# analog_gpio.net
KiCad netlist of a schematic drawn in Altium Designer
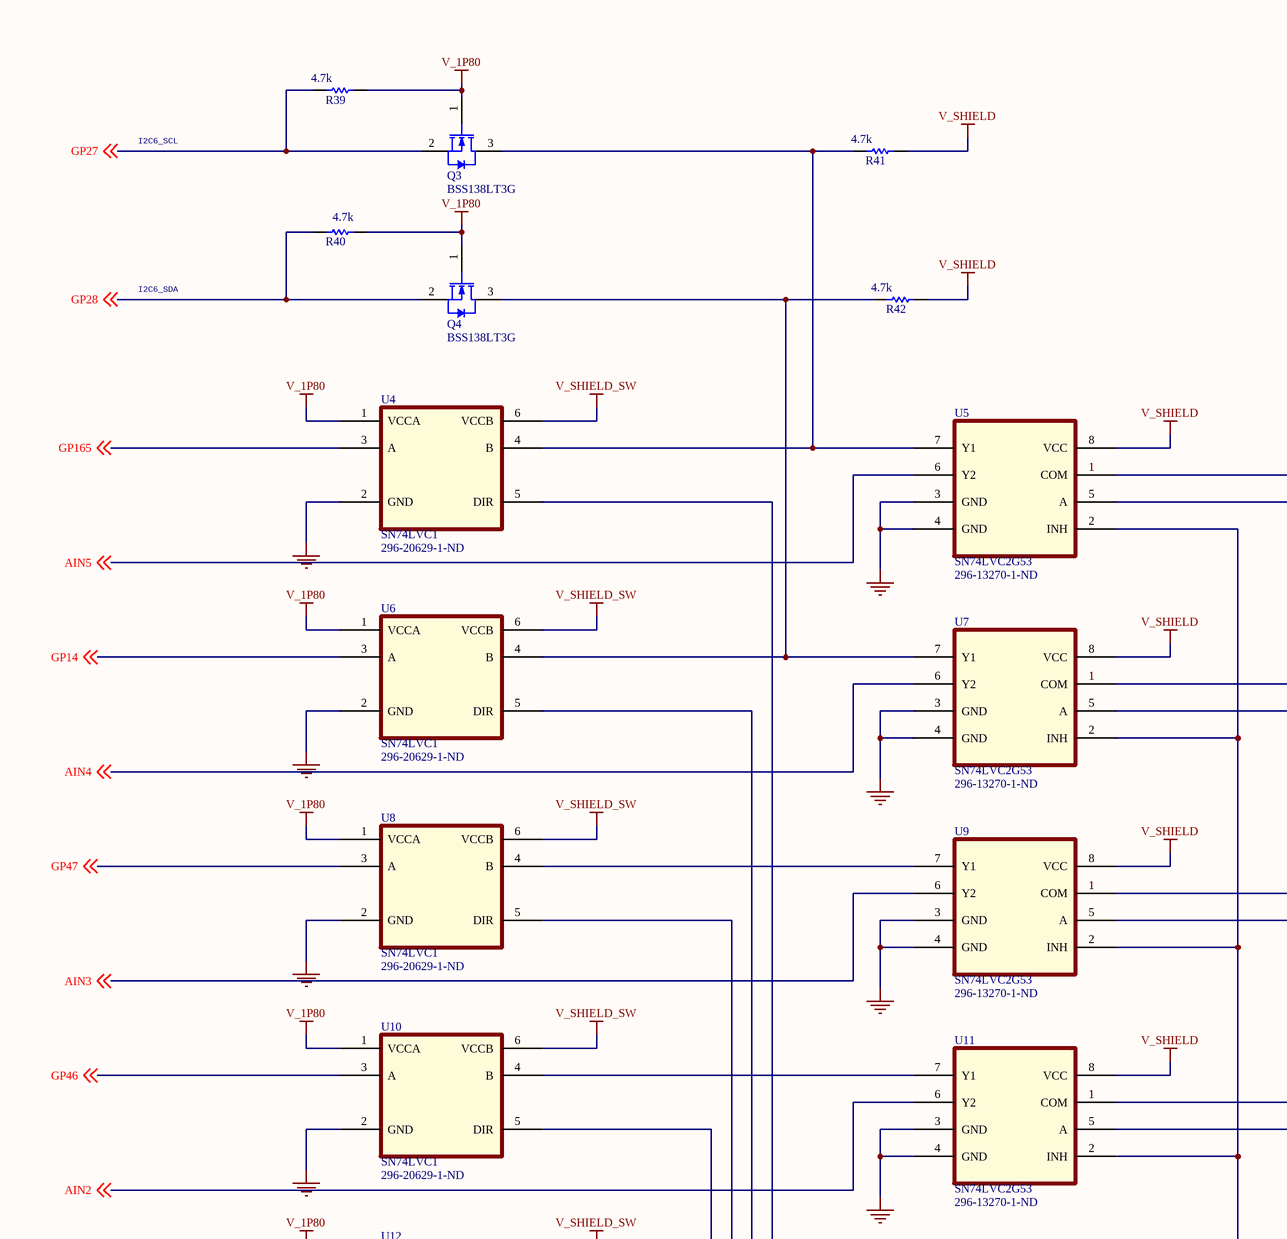
[diagram p0: analog_gpio.SchDoc, top left]
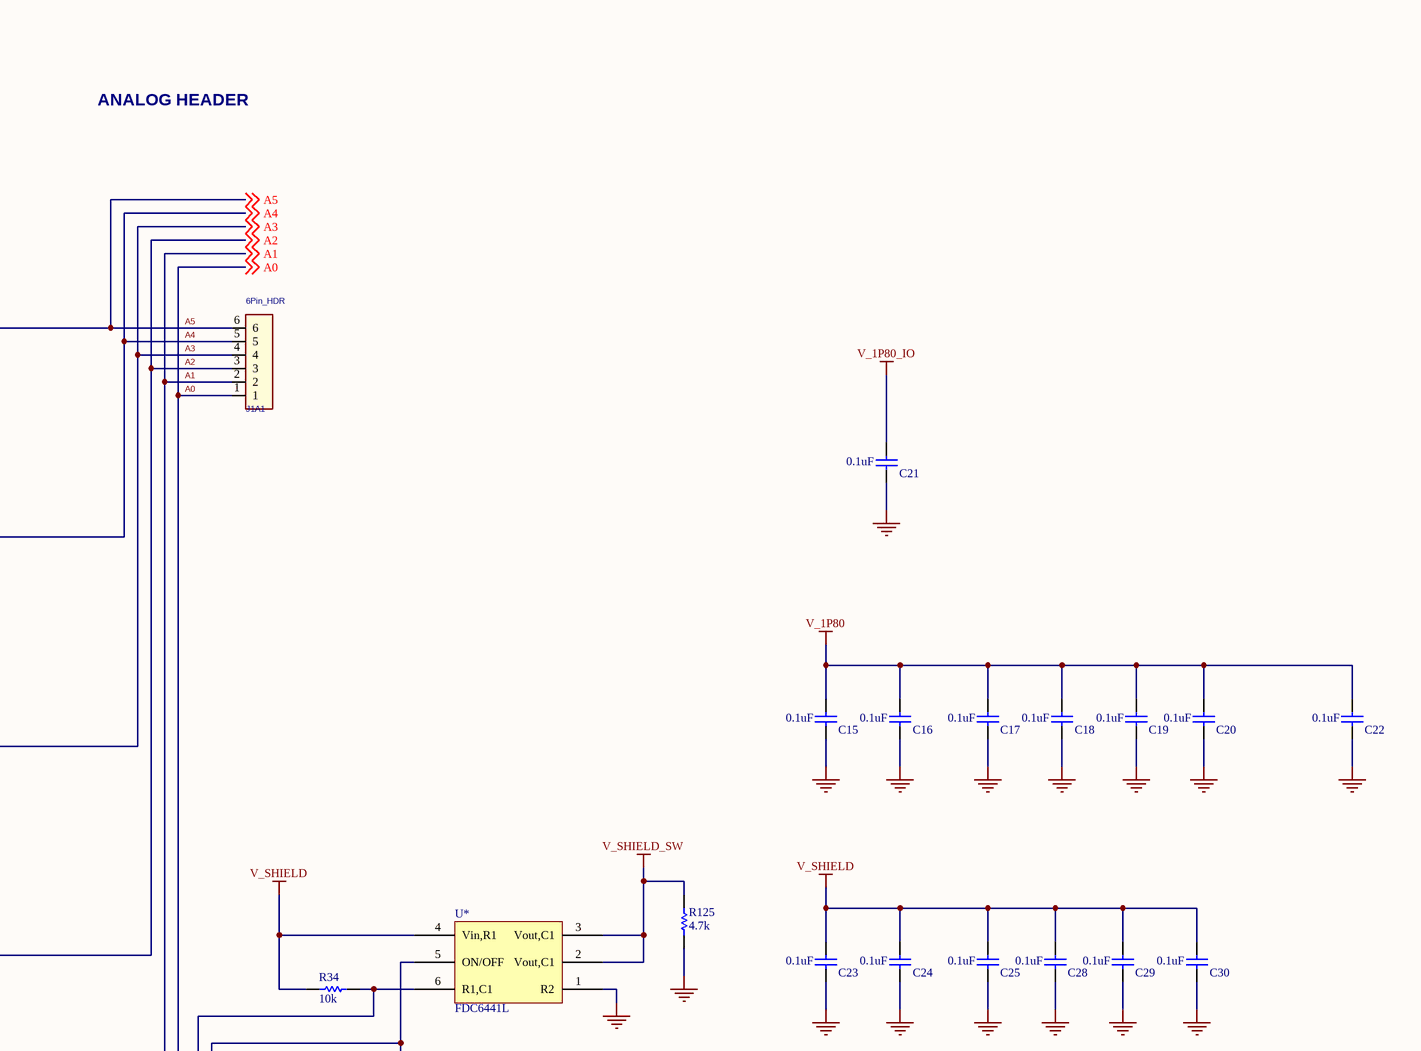
[diagram p1: analog_gpio.SchDoc, top right]
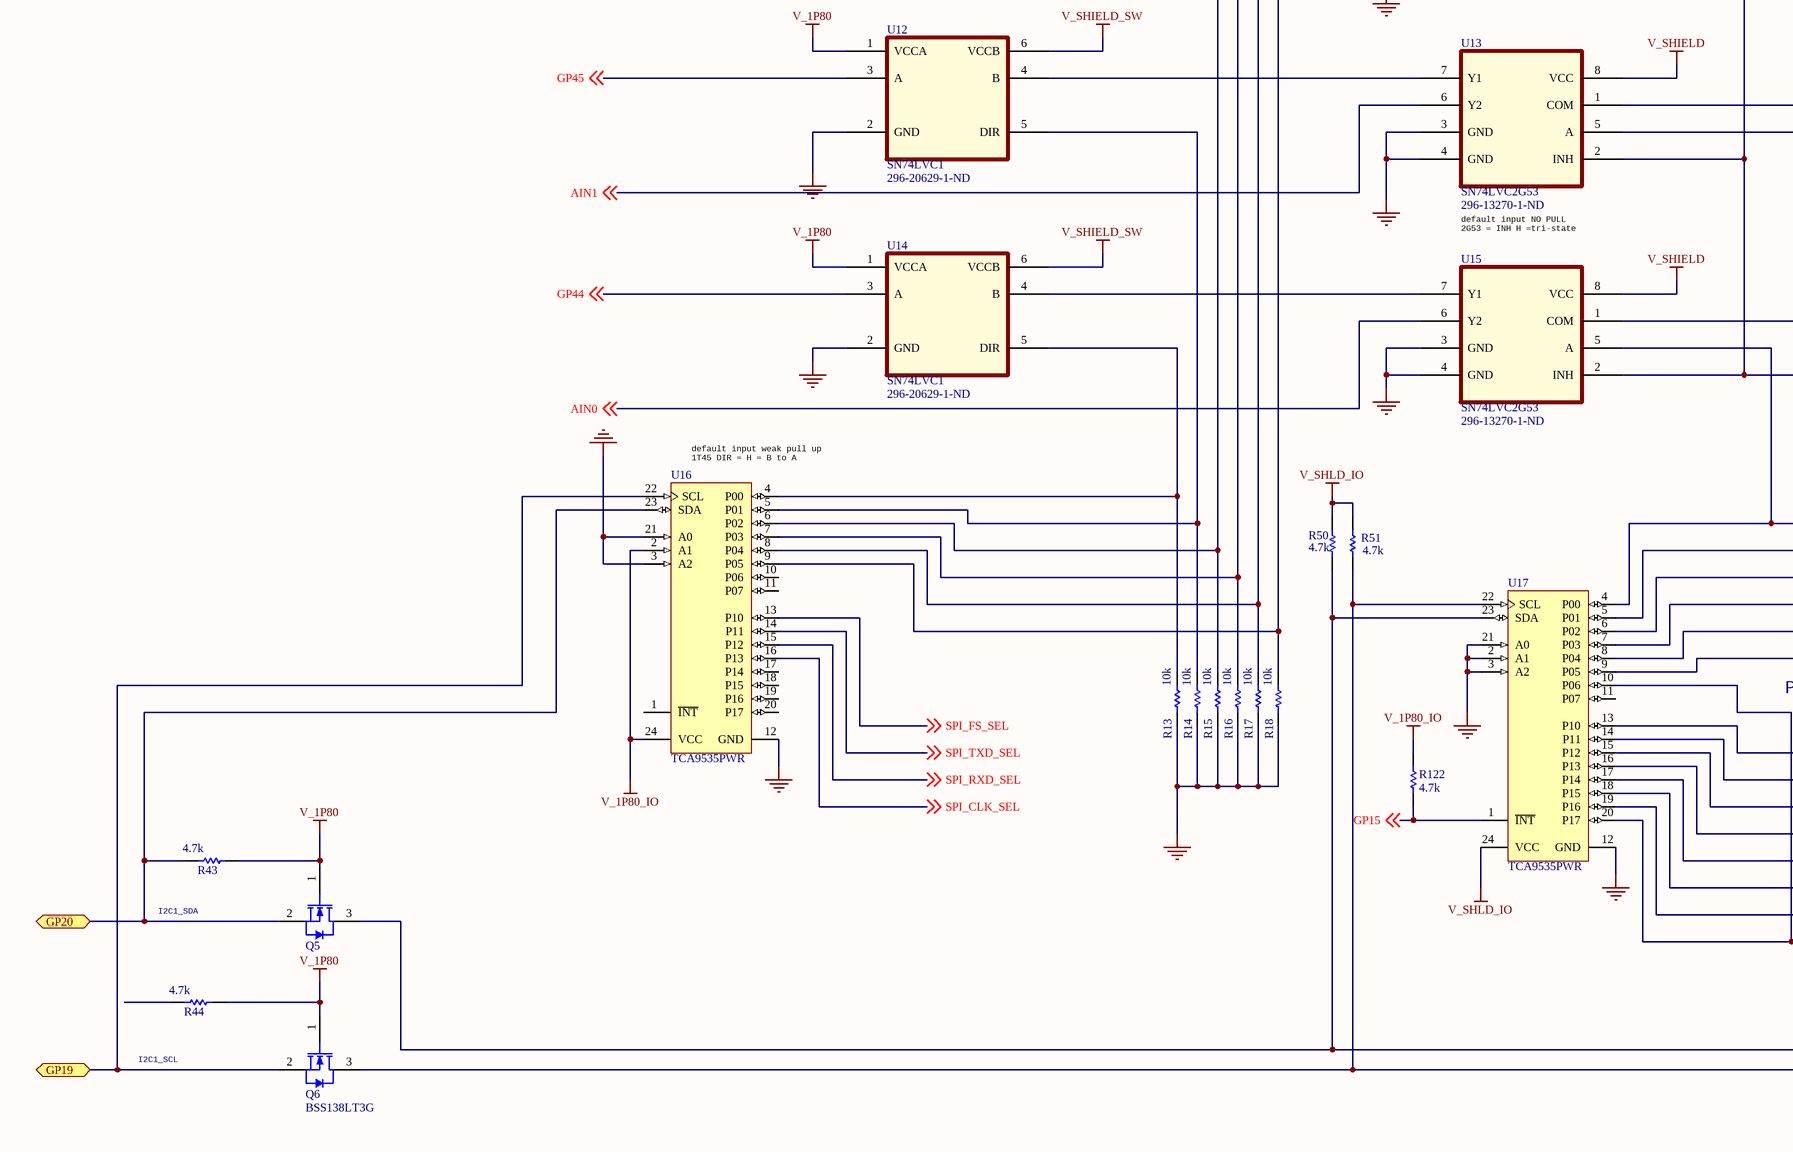
[diagram p2: analog_gpio.SchDoc, bottom left]
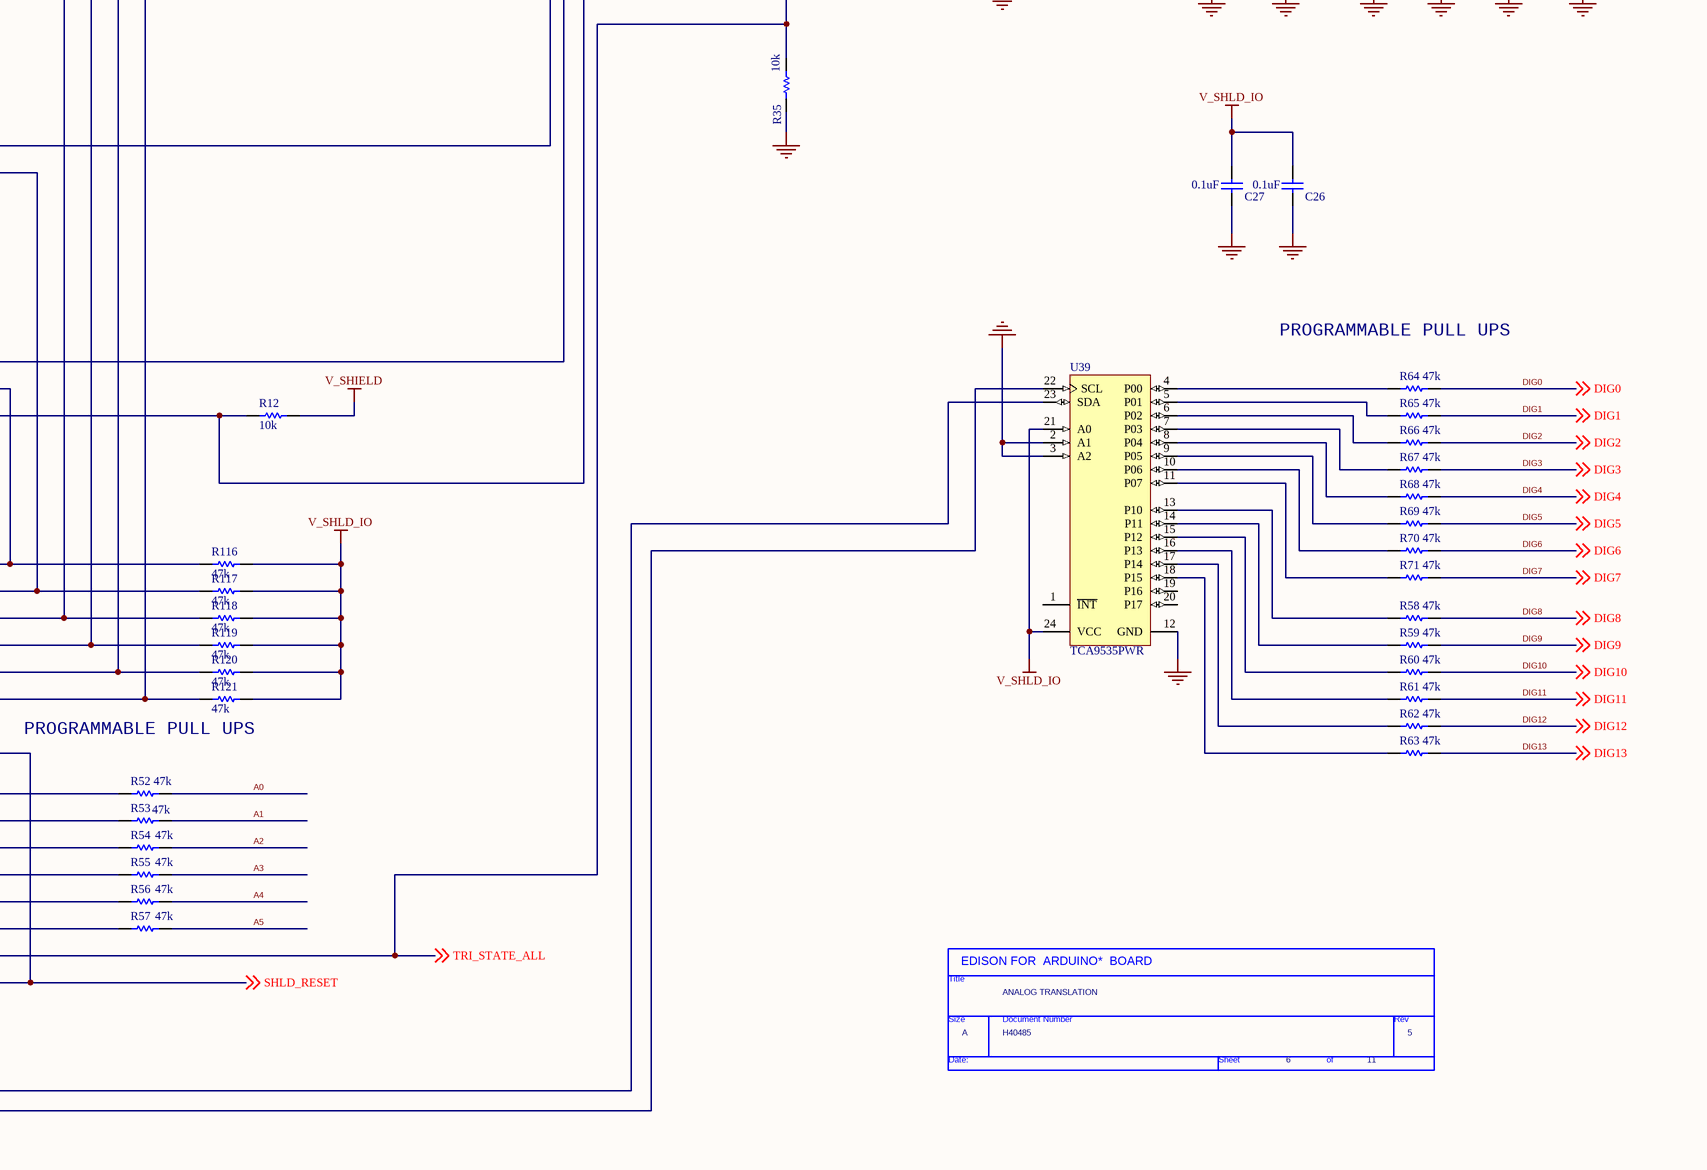
[diagram p3: analog_gpio.SchDoc, bottom right]

(export (version "E")
  (design (tool "Eeschema 10.0.6"))
  (components
    (comp (ref "*")
      (value "TitleBlock0")
      (fields
        (field (name "PAGE COUNT") "11")
        (field (name "PAGE NUMBER") "6")
        (field (name "PAGE SIZE") "A")
        (field (name "TITLE") "ANALOG TRANSLATION")
        (field (name "REVCODE") "5")
        (field (name "DOC") "H40485")
      )
      (libsource (lib "*") (part "TitleBlock0"))
    )
    (comp (ref "C15")
      (value "0.1uF")
      (footprint "CAPC0201(0603)33_L")
      (description "CAP 1.5nF 10V ±20% 0201 (0603 Metric) Thickness 0.33mm SMD")
      (fields (field (name "TOLERANCE") "±20%") (field (name "Comment") "CAP 1.5nF 10V 0201(0603)"))
      (libsource (lib "Altium Content Vault") (part "CMP-1033-00601-1"))
    )
    (comp (ref "C16")
      (value "0.1uF")
      (footprint "CAPC0201(0603)33_L")
      (description "CAP 1.5nF 10V ±20% 0201 (0603 Metric) Thickness 0.33mm SMD")
      (fields (field (name "TOLERANCE") "±20%") (field (name "Comment") "CAP 1.5nF 10V 0201(0603)"))
      (libsource (lib "Altium Content Vault") (part "CMP-1033-00601-1"))
    )
    (comp (ref "C17")
      (value "0.1uF")
      (footprint "CAPC0201(0603)33_L")
      (description "CAP 1.5nF 10V ±20% 0201 (0603 Metric) Thickness 0.33mm SMD")
      (fields (field (name "TOLERANCE") "±20%") (field (name "Comment") "CAP 1.5nF 10V 0201(0603)"))
      (libsource (lib "Altium Content Vault") (part "CMP-1033-00601-1"))
    )
    (comp (ref "C18")
      (value "0.1uF")
      (footprint "CAPC0201(0603)33_L")
      (description "CAP 1.5nF 10V ±20% 0201 (0603 Metric) Thickness 0.33mm SMD")
      (fields (field (name "TOLERANCE") "±20%") (field (name "Comment") "CAP 1.5nF 10V 0201(0603)"))
      (libsource (lib "Altium Content Vault") (part "CMP-1033-00601-1"))
    )
    (comp (ref "C19")
      (value "0.1uF")
      (footprint "CAPC0201(0603)33_L")
      (description "CAP 1.5nF 10V ±20% 0201 (0603 Metric) Thickness 0.33mm SMD")
      (fields (field (name "TOLERANCE") "±20%") (field (name "Comment") "CAP 1.5nF 10V 0201(0603)"))
      (libsource (lib "Altium Content Vault") (part "CMP-1033-00601-1"))
    )
    (comp (ref "C20")
      (value "0.1uF")
      (footprint "CAPC0201(0603)33_L")
      (description "CAP 1.5nF 10V ±20% 0201 (0603 Metric) Thickness 0.33mm SMD")
      (fields (field (name "TOLERANCE") "±20%") (field (name "Comment") "CAP 1.5nF 10V 0201(0603)"))
      (libsource (lib "Altium Content Vault") (part "CMP-1033-00601-1"))
    )
    (comp (ref "C21")
      (value "0.1uF")
      (footprint "CAPC0201(0603)33_L")
      (description "CAP 1.5nF 10V ±20% 0201 (0603 Metric) Thickness 0.33mm SMD")
      (fields (field (name "TOLERANCE") "±20%") (field (name "Comment") "CAP 1.5nF 10V 0201(0603)"))
      (libsource (lib "Altium Content Vault") (part "CMP-1033-00601-1"))
    )
    (comp (ref "C22")
      (value "0.1uF")
      (footprint "CAPC0201(0603)33_L")
      (description "CAP 1.5nF 10V ±20% 0201 (0603 Metric) Thickness 0.33mm SMD")
      (fields (field (name "TOLERANCE") "±20%") (field (name "Comment") "CAP 1.5nF 10V 0201(0603)"))
      (libsource (lib "Altium Content Vault") (part "CMP-1033-00601-1"))
    )
    (comp (ref "C23")
      (value "0.1uF")
      (footprint "CAPC0201(0603)33_L")
      (description "CAP 1.5nF 10V ±20% 0201 (0603 Metric) Thickness 0.33mm SMD")
      (fields (field (name "TOLERANCE") "±20%") (field (name "Comment") "CAP 1.5nF 10V 0201(0603)"))
      (libsource (lib "Altium Content Vault") (part "CMP-1033-00601-1"))
    )
    (comp (ref "C24")
      (value "0.1uF")
      (footprint "CAPC0201(0603)33_L")
      (description "CAP 1.5nF 10V ±20% 0201 (0603 Metric) Thickness 0.33mm SMD")
      (fields (field (name "TOLERANCE") "±20%") (field (name "Comment") "CAP 1.5nF 10V 0201(0603)"))
      (libsource (lib "Altium Content Vault") (part "CMP-1033-00601-1"))
    )
    (comp (ref "C25")
      (value "0.1uF")
      (footprint "CAPC0201(0603)33_L")
      (description "CAP 1.5nF 10V ±20% 0201 (0603 Metric) Thickness 0.33mm SMD")
      (fields (field (name "TOLERANCE") "±20%") (field (name "Comment") "CAP 1.5nF 10V 0201(0603)"))
      (libsource (lib "Altium Content Vault") (part "CMP-1033-00601-1"))
    )
    (comp (ref "C26")
      (value "0.1uF")
      (footprint "CAPC0201(0603)33_L")
      (description "CAP 1.5nF 10V ±20% 0201 (0603 Metric) Thickness 0.33mm SMD")
      (fields (field (name "TOLERANCE") "±20%") (field (name "Comment") "CAP 1.5nF 10V 0201(0603)"))
      (libsource (lib "Altium Content Vault") (part "CMP-1033-00601-1"))
    )
    (comp (ref "C27")
      (value "0.1uF")
      (footprint "CAPC0201(0603)33_L")
      (description "CAP 1.5nF 10V ±20% 0201 (0603 Metric) Thickness 0.33mm SMD")
      (fields (field (name "TOLERANCE") "±20%") (field (name "Comment") "CAP 1.5nF 10V 0201(0603)"))
      (libsource (lib "Altium Content Vault") (part "CMP-1033-00601-1"))
    )
    (comp (ref "C28")
      (value "0.1uF")
      (footprint "CAPC0201(0603)33_L")
      (description "CAP 1.5nF 10V ±20% 0201 (0603 Metric) Thickness 0.33mm SMD")
      (fields (field (name "TOLERANCE") "±20%") (field (name "Comment") "CAP 1.5nF 10V 0201(0603)"))
      (libsource (lib "Altium Content Vault") (part "CMP-1033-00601-1"))
    )
    (comp (ref "C29")
      (value "0.1uF")
      (footprint "CAPC0201(0603)33_L")
      (description "CAP 1.5nF 10V ±20% 0201 (0603 Metric) Thickness 0.33mm SMD")
      (fields (field (name "TOLERANCE") "±20%") (field (name "Comment") "CAP 1.5nF 10V 0201(0603)"))
      (libsource (lib "Altium Content Vault") (part "CMP-1033-00601-1"))
    )
    (comp (ref "C30")
      (value "0.1uF")
      (footprint "CAPC0201(0603)33_L")
      (description "CAP 1.5nF 10V ±20% 0201 (0603 Metric) Thickness 0.33mm SMD")
      (fields (field (name "TOLERANCE") "±20%") (field (name "Comment") "CAP 1.5nF 10V 0201(0603)"))
      (libsource (lib "Altium Content Vault") (part "CMP-1033-00601-1"))
    )
    (comp (ref "J1A1")
      (value "6Pin_HDR")
      (footprint "109728-038")
      (description "CONN,PLUG,VERT,1X6,2.54MM,THM,90147_1106")
      (fields (field (name "PART_NUMBER") "H46111-001"))
      (libsource (lib "*") (part "CON6,HDR,TH,0.1in,C77962-001"))
    )
    (comp (ref "Q3")
      (value "BSS138LT3G")
      (footprint "ONSC-SOT-23-3-318-08_V")
      (description "Power MOSFET, 200 mA, 50 V, N-Channel, 3-Pin SOT-23, Pb-Free, Tape and Reel")
      (fields (field (name "MANUFACTURER") "On Semiconductor"))
      (libsource (lib "Altium Content Vault") (part "CMP-1058-00765-1"))
    )
    (comp (ref "Q4")
      (value "BSS138LT3G")
      (footprint "ONSC-SOT-23-3-318-08_V")
      (description "Power MOSFET, 200 mA, 50 V, N-Channel, 3-Pin SOT-23, Pb-Free, Tape and Reel")
      (fields (field (name "MANUFACTURER") "On Semiconductor"))
      (libsource (lib "Altium Content Vault") (part "ONSC-NMOS-G1S2D3-3"))
    )
    (comp (ref "Q5")
      (value "BSS138LT3G")
      (footprint "ONSC-SOT-23-3-318-08_V")
      (description "Power MOSFET, 200 mA, 50 V, N-Channel, 3-Pin SOT-23, Pb-Free, Tape and Reel")
      (fields (field (name "MANUFACTURER") "On Semiconductor"))
      (libsource (lib "Altium Content Vault") (part "CMP-1058-00765-1"))
    )
    (comp (ref "Q6")
      (value "BSS138LT3G")
      (footprint "ONSC-SOT-23-3-318-08_V")
      (description "Power MOSFET, 200 mA, 50 V, N-Channel, 3-Pin SOT-23, Pb-Free, Tape and Reel")
      (fields (field (name "MANUFACTURER") "On Semiconductor"))
      (libsource (lib "Altium Content Vault") (part "CMP-1058-00765-1"))
    )
    (comp (ref "R12")
      (value "10k")
      (footprint "RESC0201(0603)_M")
      (description "165R 0.05W 1% 0201 (0603 Metric)  SMD")
      (fields (field (name "POWER") "0.05 W") (field (name "TOLERANCE") "1 %"))
      (libsource (lib "Altium Content Vault") (part "CMP-1010-00326-1"))
    )
    (comp (ref "R13")
      (value "10k")
      (footprint "RESC0201(0603)_M")
      (description "165R 0.05W 1% 0201 (0603 Metric)  SMD")
      (fields (field (name "POWER") "0.05 W") (field (name "TOLERANCE") "1 %"))
      (libsource (lib "Altium Content Vault") (part "CMP-1010-00326-1"))
    )
    (comp (ref "R14")
      (value "10k")
      (footprint "RESC0201(0603)_M")
      (description "165R 0.05W 1% 0201 (0603 Metric)  SMD")
      (fields (field (name "POWER") "0.05 W") (field (name "TOLERANCE") "1 %"))
      (libsource (lib "Altium Content Vault") (part "CMP-1010-00326-1"))
    )
    (comp (ref "R15")
      (value "10k")
      (footprint "RESC0201(0603)_M")
      (description "165R 0.05W 1% 0201 (0603 Metric)  SMD")
      (fields (field (name "POWER") "0.05 W") (field (name "TOLERANCE") "1 %"))
      (libsource (lib "Altium Content Vault") (part "CMP-1010-00326-1"))
    )
    (comp (ref "R16")
      (value "10k")
      (footprint "RESC0201(0603)_M")
      (description "165R 0.05W 1% 0201 (0603 Metric)  SMD")
      (fields (field (name "POWER") "0.05 W") (field (name "TOLERANCE") "1 %"))
      (libsource (lib "Altium Content Vault") (part "CMP-1010-00326-1"))
    )
    (comp (ref "R17")
      (value "10k")
      (footprint "RESC0201(0603)_M")
      (description "165R 0.05W 1% 0201 (0603 Metric)  SMD")
      (fields (field (name "POWER") "0.05 W") (field (name "TOLERANCE") "1 %"))
      (libsource (lib "Altium Content Vault") (part "CMP-1010-00326-1"))
    )
    (comp (ref "R18")
      (value "10k")
      (footprint "RESC0201(0603)_M")
      (description "165R 0.05W 1% 0201 (0603 Metric)  SMD")
      (fields (field (name "POWER") "0.05 W") (field (name "TOLERANCE") "1 %"))
      (libsource (lib "Altium Content Vault") (part "CMP-1010-00326-1"))
    )
    (comp (ref "R34")
      (value "10k")
      (footprint "RESC0201(0603)_M")
      (description "165R 0.05W 1% 0201 (0603 Metric)  SMD")
      (fields (field (name "POWER") "0.05 W") (field (name "TOLERANCE") "1 %"))
      (libsource (lib "Altium Content Vault") (part "CMP-1010-00326-1"))
    )
    (comp (ref "R35")
      (value "10k")
      (footprint "RESC0201(0603)_M")
      (description "165R 0.05W 1% 0201 (0603 Metric)  SMD")
      (fields (field (name "POWER") "0.05 W") (field (name "TOLERANCE") "1 %"))
      (libsource (lib "Altium Content Vault") (part "CMP-1010-00326-1"))
    )
    (comp (ref "R39")
      (value "4.7k")
      (footprint "RESC0201(0603)_N")
      (description "4K7 0.05W 1% 0201 (0603 Metric)  SMD")
      (fields (field (name "TOLERANCE") "1 %") (field (name "POWER") "0.05 W"))
      (libsource (lib "Altium Content Vault") (part "CMP-1010-00492-1"))
    )
    (comp (ref "R40")
      (value "4.7k")
      (footprint "RESC0201(0603)_N")
      (description "4K7 0.05W 1% 0201 (0603 Metric)  SMD")
      (fields (field (name "TOLERANCE") "1 %") (field (name "POWER") "0.05 W"))
      (libsource (lib "Altium Content Vault") (part "CMP-1010-00492-1"))
    )
    (comp (ref "R41")
      (value "4.7k")
      (footprint "RESC0201(0603)_N")
      (description "4K7 0.05W 1% 0201 (0603 Metric)  SMD")
      (fields (field (name "TOLERANCE") "1 %") (field (name "POWER") "0.05 W"))
      (libsource (lib "Altium Content Vault") (part "CMP-1010-00492-1"))
    )
    (comp (ref "R42")
      (value "4.7k")
      (footprint "RESC0201(0603)_N")
      (description "4K7 0.05W 1% 0201 (0603 Metric)  SMD")
      (fields (field (name "TOLERANCE") "1 %") (field (name "POWER") "0.05 W"))
      (libsource (lib "Altium Content Vault") (part "CMP-1010-00492-1"))
    )
    (comp (ref "R43")
      (value "4.7k")
      (footprint "RESC0201(0603)_N")
      (description "4K7 0.05W 1% 0201 (0603 Metric)  SMD")
      (fields (field (name "TOLERANCE") "1 %") (field (name "POWER") "0.05 W"))
      (libsource (lib "Altium Content Vault") (part "CMP-1010-00492-1"))
    )
    (comp (ref "R44")
      (value "4.7k")
      (footprint "RESC0201(0603)_N")
      (description "4K7 0.05W 1% 0201 (0603 Metric)  SMD")
      (fields (field (name "TOLERANCE") "1 %") (field (name "POWER") "0.05 W"))
      (libsource (lib "Altium Content Vault") (part "CMP-1010-00492-1"))
    )
    (comp (ref "R50")
      (value "4.7k")
      (footprint "RESC0201(0603)_N")
      (description "4K7 0.05W 1% 0201 (0603 Metric)  SMD")
      (fields (field (name "TOLERANCE") "1 %") (field (name "POWER") "0.05 W"))
      (libsource (lib "Altium Content Vault") (part "CMP-1010-00492-1"))
    )
    (comp (ref "R51")
      (value "4.7k")
      (footprint "RESC0201(0603)_N")
      (description "4K7 0.05W 1% 0201 (0603 Metric)  SMD")
      (fields (field (name "TOLERANCE") "1 %") (field (name "POWER") "0.05 W"))
      (libsource (lib "Altium Content Vault") (part "CMP-1010-00492-1"))
    )
    (comp (ref "R52")
      (value "47k")
      (footprint "RESC0201(0603)_N")
      (description "47K 0.05W 1% 0201 (0603 Metric)  SMD")
      (fields (field (name "TOLERANCE") "1 %") (field (name "POWER") "0.05 W"))
      (libsource (lib "Altium Content Vault") (part "CMP-1010-00605-1"))
    )
    (comp (ref "R53")
      (value "47k")
      (footprint "RESC0201(0603)_N")
      (description "47K 0.05W 1% 0201 (0603 Metric)  SMD")
      (fields (field (name "TOLERANCE") "1 %") (field (name "POWER") "0.05 W"))
      (libsource (lib "Altium Content Vault") (part "CMP-1010-00605-1"))
    )
    (comp (ref "R54")
      (value "47k")
      (footprint "RESC0201(0603)_N")
      (description "47K 0.05W 1% 0201 (0603 Metric)  SMD")
      (fields (field (name "TOLERANCE") "1 %") (field (name "POWER") "0.05 W"))
      (libsource (lib "Altium Content Vault") (part "CMP-1010-00605-1"))
    )
    (comp (ref "R55")
      (value "47k")
      (footprint "RESC0201(0603)_N")
      (description "47K 0.05W 1% 0201 (0603 Metric)  SMD")
      (fields (field (name "TOLERANCE") "1 %") (field (name "POWER") "0.05 W"))
      (libsource (lib "Altium Content Vault") (part "CMP-1010-00605-1"))
    )
    (comp (ref "R56")
      (value "47k")
      (footprint "RESC0201(0603)_N")
      (description "47K 0.05W 1% 0201 (0603 Metric)  SMD")
      (fields (field (name "TOLERANCE") "1 %") (field (name "POWER") "0.05 W"))
      (libsource (lib "Altium Content Vault") (part "CMP-1010-00605-1"))
    )
    (comp (ref "R57")
      (value "47k")
      (footprint "RESC0201(0603)_N")
      (description "47K 0.05W 1% 0201 (0603 Metric)  SMD")
      (fields (field (name "TOLERANCE") "1 %") (field (name "POWER") "0.05 W"))
      (libsource (lib "Altium Content Vault") (part "CMP-1010-00605-1"))
    )
    (comp (ref "R58")
      (value "47k")
      (footprint "RESC0201(0603)_N")
      (description "47K 0.05W 1% 0201 (0603 Metric)  SMD")
      (fields (field (name "TOLERANCE") "1 %") (field (name "POWER") "0.05 W"))
      (libsource (lib "Altium Content Vault") (part "CMP-1010-00605-1"))
    )
    (comp (ref "R59")
      (value "47k")
      (footprint "RESC0201(0603)_N")
      (description "47K 0.05W 1% 0201 (0603 Metric)  SMD")
      (fields (field (name "TOLERANCE") "1 %") (field (name "POWER") "0.05 W"))
      (libsource (lib "Altium Content Vault") (part "CMP-1010-00605-1"))
    )
    (comp (ref "R60")
      (value "47k")
      (footprint "RESC0201(0603)_N")
      (description "47K 0.05W 1% 0201 (0603 Metric)  SMD")
      (fields (field (name "TOLERANCE") "1 %") (field (name "POWER") "0.05 W"))
      (libsource (lib "Altium Content Vault") (part "CMP-1010-00605-1"))
    )
    (comp (ref "R61")
      (value "47k")
      (footprint "RESC0201(0603)_N")
      (description "47K 0.05W 1% 0201 (0603 Metric)  SMD")
      (fields (field (name "TOLERANCE") "1 %") (field (name "POWER") "0.05 W"))
      (libsource (lib "Altium Content Vault") (part "CMP-1010-00605-1"))
    )
    (comp (ref "R62")
      (value "47k")
      (footprint "RESC0201(0603)_N")
      (description "47K 0.05W 1% 0201 (0603 Metric)  SMD")
      (fields (field (name "TOLERANCE") "1 %") (field (name "POWER") "0.05 W"))
      (libsource (lib "Altium Content Vault") (part "CMP-1010-00605-1"))
    )
    (comp (ref "R63")
      (value "47k")
      (footprint "RESC0201(0603)_N")
      (description "47K 0.05W 1% 0201 (0603 Metric)  SMD")
      (fields (field (name "TOLERANCE") "1 %") (field (name "POWER") "0.05 W"))
      (libsource (lib "Altium Content Vault") (part "CMP-1010-00605-1"))
    )
    (comp (ref "R64")
      (value "47k")
      (footprint "RESC0201(0603)_N")
      (description "47K 0.05W 1% 0201 (0603 Metric)  SMD")
      (fields (field (name "TOLERANCE") "1 %") (field (name "POWER") "0.05 W"))
      (libsource (lib "Altium Content Vault") (part "CMP-1010-00605-1"))
    )
    (comp (ref "R65")
      (value "47k")
      (footprint "RESC0201(0603)_N")
      (description "47K 0.05W 1% 0201 (0603 Metric)  SMD")
      (fields (field (name "TOLERANCE") "1 %") (field (name "POWER") "0.05 W"))
      (libsource (lib "Altium Content Vault") (part "CMP-1010-00605-1"))
    )
    (comp (ref "R66")
      (value "47k")
      (footprint "RESC0201(0603)_N")
      (description "47K 0.05W 1% 0201 (0603 Metric)  SMD")
      (fields (field (name "TOLERANCE") "1 %") (field (name "POWER") "0.05 W"))
      (libsource (lib "Altium Content Vault") (part "CMP-1010-00605-1"))
    )
    (comp (ref "R67")
      (value "47k")
      (footprint "RESC0201(0603)_N")
      (description "47K 0.05W 1% 0201 (0603 Metric)  SMD")
      (fields (field (name "TOLERANCE") "1 %") (field (name "POWER") "0.05 W"))
      (libsource (lib "Altium Content Vault") (part "CMP-1010-00605-1"))
    )
    (comp (ref "R68")
      (value "47k")
      (footprint "RESC0201(0603)_N")
      (description "47K 0.05W 1% 0201 (0603 Metric)  SMD")
      (fields (field (name "TOLERANCE") "1 %") (field (name "POWER") "0.05 W"))
      (libsource (lib "Altium Content Vault") (part "CMP-1010-00605-1"))
    )
    (comp (ref "R69")
      (value "47k")
      (footprint "RESC0201(0603)_N")
      (description "47K 0.05W 1% 0201 (0603 Metric)  SMD")
      (fields (field (name "TOLERANCE") "1 %") (field (name "POWER") "0.05 W"))
      (libsource (lib "Altium Content Vault") (part "CMP-1010-00605-1"))
    )
    (comp (ref "R70")
      (value "47k")
      (footprint "RESC0201(0603)_N")
      (description "47K 0.05W 1% 0201 (0603 Metric)  SMD")
      (fields (field (name "TOLERANCE") "1 %") (field (name "POWER") "0.05 W"))
      (libsource (lib "Altium Content Vault") (part "CMP-1010-00605-1"))
    )
    (comp (ref "R71")
      (value "47k")
      (footprint "RESC0201(0603)_N")
      (description "47K 0.05W 1% 0201 (0603 Metric)  SMD")
      (fields (field (name "TOLERANCE") "1 %") (field (name "POWER") "0.05 W"))
      (libsource (lib "Altium Content Vault") (part "CMP-1010-00605-1"))
    )
    (comp (ref "R116")
      (value "47k")
      (footprint "RESC0201(0603)_N")
      (description "47K 0.05W 1% 0201 (0603 Metric)  SMD")
      (fields (field (name "TOLERANCE") "1 %") (field (name "POWER") "0.05 W"))
      (libsource (lib "Altium Content Vault") (part "CMP-1010-00605-1"))
    )
    (comp (ref "R117")
      (value "47k")
      (footprint "RESC0201(0603)_N")
      (description "47K 0.05W 1% 0201 (0603 Metric)  SMD")
      (fields (field (name "TOLERANCE") "1 %") (field (name "POWER") "0.05 W"))
      (libsource (lib "Altium Content Vault") (part "CMP-1010-00605-1"))
    )
    (comp (ref "R118")
      (value "47k")
      (footprint "RESC0201(0603)_N")
      (description "47K 0.05W 1% 0201 (0603 Metric)  SMD")
      (fields (field (name "TOLERANCE") "1 %") (field (name "POWER") "0.05 W"))
      (libsource (lib "Altium Content Vault") (part "CMP-1010-00605-1"))
    )
    (comp (ref "R119")
      (value "47k")
      (footprint "RESC0201(0603)_N")
      (description "47K 0.05W 1% 0201 (0603 Metric)  SMD")
      (fields (field (name "TOLERANCE") "1 %") (field (name "POWER") "0.05 W"))
      (libsource (lib "Altium Content Vault") (part "CMP-1010-00605-1"))
    )
    (comp (ref "R120")
      (value "47k")
      (footprint "RESC0201(0603)_N")
      (description "47K 0.05W 1% 0201 (0603 Metric)  SMD")
      (fields (field (name "TOLERANCE") "1 %") (field (name "POWER") "0.05 W"))
      (libsource (lib "Altium Content Vault") (part "CMP-1010-00605-1"))
    )
    (comp (ref "R121")
      (value "47k")
      (footprint "RESC0201(0603)_N")
      (description "47K 0.05W 1% 0201 (0603 Metric)  SMD")
      (fields (field (name "TOLERANCE") "1 %") (field (name "POWER") "0.05 W"))
      (libsource (lib "Altium Content Vault") (part "CMP-1010-00605-1"))
    )
    (comp (ref "R122")
      (value "4.7k")
      (footprint "RESC0201(0603)_N")
      (description "4K7 0.05W 1% 0201 (0603 Metric)  SMD")
      (fields (field (name "TOLERANCE") "1 %") (field (name "POWER") "0.05 W"))
      (libsource (lib "Altium Content Vault") (part "CMP-1010-00492-1"))
    )
    (comp (ref "R125")
      (value "4.7k")
      (footprint "RESC0201(0603)_N")
      (description "4K7 0.05W 1% 0201 (0603 Metric)  SMD")
      (fields (field (name "TOLERANCE") "1 %") (field (name "POWER") "0.05 W"))
      (libsource (lib "Altium Content Vault") (part "CMP-1010-00492-1"))
    )
    (comp (ref "U*")
      (value "FDC6441L")
      (footprint "SUPERSOP6")
      (description "Load Switch")
      (libsource (lib "elevate_lib") (part "FDC6331L"))
    )
    (comp (ref "U4")
      (value "SN74LVC1")
      (footprint "R-PDSO-N6")
      (fields (field (name "SUPPLIER PART NUMBER 1") "296-20629-1-ND"))
      (libsource (lib "elevate_lib") (part "SN74LVC1"))
    )
    (comp (ref "U5")
      (value "SN74LVC2G53")
      (footprint "S-PSDO-8")
      (fields (field (name "SUPPLIER PART NUMBER 1") "296-13270-1-ND"))
      (libsource (lib "elevate_lib") (part "SN74LVC2G53"))
    )
    (comp (ref "U6")
      (value "SN74LVC1")
      (footprint "R-PDSO-N6")
      (fields (field (name "SUPPLIER PART NUMBER 1") "296-20629-1-ND"))
      (libsource (lib "elevate_lib") (part "SN74LVC1"))
    )
    (comp (ref "U7")
      (value "SN74LVC2G53")
      (footprint "S-PSDO-8")
      (fields (field (name "SUPPLIER PART NUMBER 1") "296-13270-1-ND"))
      (libsource (lib "elevate_lib") (part "SN74LVC2G53"))
    )
    (comp (ref "U8")
      (value "SN74LVC1")
      (footprint "R-PDSO-N6")
      (fields (field (name "SUPPLIER PART NUMBER 1") "296-20629-1-ND"))
      (libsource (lib "elevate_lib") (part "SN74LVC1"))
    )
    (comp (ref "U9")
      (value "SN74LVC2G53")
      (footprint "S-PSDO-8")
      (fields (field (name "SUPPLIER PART NUMBER 1") "296-13270-1-ND"))
      (libsource (lib "elevate_lib") (part "SN74LVC2G53"))
    )
    (comp (ref "U10")
      (value "SN74LVC1")
      (footprint "R-PDSO-N6")
      (fields (field (name "SUPPLIER PART NUMBER 1") "296-20629-1-ND"))
      (libsource (lib "elevate_lib") (part "SN74LVC1"))
    )
    (comp (ref "U11")
      (value "SN74LVC2G53")
      (footprint "S-PSDO-8")
      (fields (field (name "SUPPLIER PART NUMBER 1") "296-13270-1-ND"))
      (libsource (lib "elevate_lib") (part "SN74LVC2G53"))
    )
    (comp (ref "U12")
      (value "SN74LVC1")
      (footprint "R-PDSO-N6")
      (fields (field (name "SUPPLIER PART NUMBER 1") "296-20629-1-ND"))
      (libsource (lib "elevate_lib") (part "SN74LVC1"))
    )
    (comp (ref "U13")
      (value "SN74LVC2G53")
      (footprint "S-PSDO-8")
      (fields (field (name "SUPPLIER PART NUMBER 1") "296-13270-1-ND"))
      (libsource (lib "elevate_lib") (part "SN74LVC2G53"))
    )
    (comp (ref "U14")
      (value "SN74LVC1")
      (footprint "R-PDSO-N6")
      (fields (field (name "SUPPLIER PART NUMBER 1") "296-20629-1-ND"))
      (libsource (lib "elevate_lib") (part "SN74LVC1"))
    )
    (comp (ref "U15")
      (value "SN74LVC2G53")
      (footprint "S-PSDO-8")
      (fields (field (name "SUPPLIER PART NUMBER 1") "296-13270-1-ND"))
      (libsource (lib "elevate_lib") (part "SN74LVC2G53"))
    )
    (comp (ref "U16")
      (value "TCA9535PWR")
      (footprint "PW24_N")
      (fields (field (name "MANUFACTURER") "Texas Instruments"))
      (libsource (lib "Altium Content Vault") (part "TI-TCA9535-TSSOP_PW-24"))
    )
    (comp (ref "U17")
      (value "TCA9535PWR")
      (footprint "PW24_N")
      (fields (field (name "MANUFACTURER") "Texas Instruments"))
      (libsource (lib "Altium Content Vault") (part "TI-TCA9535-TSSOP_PW-24"))
    )
    (comp (ref "U39")
      (value "TCA9535PWR")
      (footprint "PW24_N")
      (fields (field (name "MANUFACTURER") "Texas Instruments"))
      (libsource (lib "Altium Content Vault") (part "TI-TCA9535-TSSOP_PW-24"))
    )
  )
  (nets
    (net (code "1") (name "/GP19") (class "Default")
      (node (ref "Q6") (pin "2") (pinfunction "S_2") (pintype "passive"))
      (node (ref "U16") (pin "22") (pinfunction "SCL_22") (pintype "input"))
    )
    (net (code "2") (name "/GP20") (class "Default")
      (node (ref "Q5") (pin "2") (pinfunction "S_2") (pintype "passive"))
      (node (ref "R43") (pin "2") (pinfunction "2_2") (pintype "passive"))
      (node (ref "U16") (pin "23") (pinfunction "SDA_23") (pintype "bidirectional"))
    )
    (net (code "3") (name "A0") (class "Default")
      (node (ref "J1A1") (pin "1") (pinfunction "1_1") (pintype "passive"))
      (node (ref "R52") (pin "1") (pinfunction "1_1") (pintype "passive"))
      (node (ref "U15") (pin "1") (pinfunction "COM_1") (pintype "passive"))
    )
    (net (code "4") (name "A1") (class "Default")
      (node (ref "J1A1") (pin "2") (pinfunction "2_2") (pintype "passive"))
      (node (ref "R53") (pin "1") (pinfunction "1_1") (pintype "passive"))
      (node (ref "U13") (pin "1") (pinfunction "COM_1") (pintype "passive"))
    )
    (net (code "5") (name "A2") (class "Default")
      (node (ref "J1A1") (pin "3") (pinfunction "3_3") (pintype "passive"))
      (node (ref "R54") (pin "1") (pinfunction "1_1") (pintype "passive"))
      (node (ref "U11") (pin "1") (pinfunction "COM_1") (pintype "passive"))
    )
    (net (code "6") (name "A3") (class "Default")
      (node (ref "J1A1") (pin "4") (pinfunction "4_4") (pintype "passive"))
      (node (ref "R55") (pin "1") (pinfunction "1_1") (pintype "passive"))
      (node (ref "U9") (pin "1") (pinfunction "COM_1") (pintype "passive"))
    )
    (net (code "7") (name "A4") (class "Default")
      (node (ref "J1A1") (pin "5") (pinfunction "5_5") (pintype "passive"))
      (node (ref "R56") (pin "1") (pinfunction "1_1") (pintype "passive"))
      (node (ref "U7") (pin "1") (pinfunction "COM_1") (pintype "passive"))
    )
    (net (code "8") (name "A5") (class "Default")
      (node (ref "J1A1") (pin "6") (pinfunction "6_6") (pintype "passive"))
      (node (ref "R57") (pin "1") (pinfunction "1_1") (pintype "passive"))
      (node (ref "U5") (pin "1") (pinfunction "COM_1") (pintype "passive"))
    )
    (net (code "9") (name "AIN0") (class "Default")
      (node (ref "U15") (pin "6") (pinfunction "Y2_6") (pintype "passive"))
    )
    (net (code "10") (name "AIN1") (class "Default")
      (node (ref "U13") (pin "6") (pinfunction "Y2_6") (pintype "passive"))
    )
    (net (code "11") (name "AIN2") (class "Default")
      (node (ref "U11") (pin "6") (pinfunction "Y2_6") (pintype "passive"))
    )
    (net (code "12") (name "AIN3") (class "Default")
      (node (ref "U9") (pin "6") (pinfunction "Y2_6") (pintype "passive"))
    )
    (net (code "13") (name "AIN4") (class "Default")
      (node (ref "U7") (pin "6") (pinfunction "Y2_6") (pintype "passive"))
    )
    (net (code "14") (name "AIN5") (class "Default")
      (node (ref "U5") (pin "6") (pinfunction "Y2_6") (pintype "passive"))
    )
    (net (code "15") (name "DIG0") (class "Default")
      (node (ref "R64") (pin "1") (pinfunction "1_1") (pintype "passive"))
    )
    (net (code "16") (name "DIG1") (class "Default")
      (node (ref "R65") (pin "1") (pinfunction "1_1") (pintype "passive"))
    )
    (net (code "17") (name "DIG2") (class "Default")
      (node (ref "R66") (pin "1") (pinfunction "1_1") (pintype "passive"))
    )
    (net (code "18") (name "DIG3") (class "Default")
      (node (ref "R67") (pin "1") (pinfunction "1_1") (pintype "passive"))
    )
    (net (code "19") (name "DIG4") (class "Default")
      (node (ref "R68") (pin "1") (pinfunction "1_1") (pintype "passive"))
    )
    (net (code "20") (name "DIG5") (class "Default")
      (node (ref "R69") (pin "1") (pinfunction "1_1") (pintype "passive"))
    )
    (net (code "21") (name "DIG6") (class "Default")
      (node (ref "R70") (pin "1") (pinfunction "1_1") (pintype "passive"))
    )
    (net (code "22") (name "DIG7") (class "Default")
      (node (ref "R71") (pin "1") (pinfunction "1_1") (pintype "passive"))
    )
    (net (code "23") (name "DIG8") (class "Default")
      (node (ref "R58") (pin "1") (pinfunction "1_1") (pintype "passive"))
    )
    (net (code "24") (name "DIG9") (class "Default")
      (node (ref "R59") (pin "1") (pinfunction "1_1") (pintype "passive"))
    )
    (net (code "25") (name "DIG10") (class "Default")
      (node (ref "R60") (pin "1") (pinfunction "1_1") (pintype "passive"))
    )
    (net (code "26") (name "DIG11") (class "Default")
      (node (ref "R61") (pin "1") (pinfunction "1_1") (pintype "passive"))
    )
    (net (code "27") (name "DIG12") (class "Default")
      (node (ref "R62") (pin "1") (pinfunction "1_1") (pintype "passive"))
    )
    (net (code "28") (name "DIG13") (class "Default")
      (node (ref "R63") (pin "1") (pinfunction "1_1") (pintype "passive"))
    )
    (net (code "29") (name "GND") (class "Default")
      (node (ref "C15") (pin "1") (pinfunction "1_1") (pintype "passive"))
      (node (ref "C16") (pin "1") (pinfunction "1_1") (pintype "passive"))
      (node (ref "C17") (pin "1") (pinfunction "1_1") (pintype "passive"))
      (node (ref "C18") (pin "1") (pinfunction "1_1") (pintype "passive"))
      (node (ref "C19") (pin "1") (pinfunction "1_1") (pintype "passive"))
      (node (ref "C20") (pin "1") (pinfunction "1_1") (pintype "passive"))
      (node (ref "C21") (pin "1") (pinfunction "1_1") (pintype "passive"))
      (node (ref "C22") (pin "1") (pinfunction "1_1") (pintype "passive"))
      (node (ref "C23") (pin "1") (pinfunction "1_1") (pintype "passive"))
      (node (ref "C24") (pin "1") (pinfunction "1_1") (pintype "passive"))
      (node (ref "C25") (pin "1") (pinfunction "1_1") (pintype "passive"))
      (node (ref "C26") (pin "1") (pinfunction "1_1") (pintype "passive"))
      (node (ref "C27") (pin "1") (pinfunction "1_1") (pintype "passive"))
      (node (ref "C28") (pin "1") (pinfunction "1_1") (pintype "passive"))
      (node (ref "C29") (pin "1") (pinfunction "1_1") (pintype "passive"))
      (node (ref "C30") (pin "1") (pinfunction "1_1") (pintype "passive"))
      (node (ref "R125") (pin "2") (pinfunction "2_2") (pintype "passive"))
      (node (ref "R13") (pin "2") (pinfunction "2_2") (pintype "passive"))
      (node (ref "R14") (pin "2") (pinfunction "2_2") (pintype "passive"))
      (node (ref "R15") (pin "2") (pinfunction "2_2") (pintype "passive"))
      (node (ref "R16") (pin "2") (pinfunction "2_2") (pintype "passive"))
      (node (ref "R17") (pin "2") (pinfunction "2_2") (pintype "passive"))
      (node (ref "R18") (pin "2") (pinfunction "2_2") (pintype "passive"))
      (node (ref "R35") (pin "2") (pinfunction "2_2") (pintype "passive"))
      (node (ref "U*") (pin "1") (pinfunction "R2_1") (pintype "passive"))
      (node (ref "U10") (pin "2") (pinfunction "GND_2") (pintype "passive"))
      (node (ref "U11") (pin "3") (pinfunction "GND_3") (pintype "passive"))
      (node (ref "U11") (pin "4") (pinfunction "GND_4") (pintype "passive"))
      (node (ref "U12") (pin "2") (pinfunction "GND_2") (pintype "passive"))
      (node (ref "U13") (pin "3") (pinfunction "GND_3") (pintype "passive"))
      (node (ref "U13") (pin "4") (pinfunction "GND_4") (pintype "passive"))
      (node (ref "U14") (pin "2") (pinfunction "GND_2") (pintype "passive"))
      (node (ref "U15") (pin "3") (pinfunction "GND_3") (pintype "passive"))
      (node (ref "U15") (pin "4") (pinfunction "GND_4") (pintype "passive"))
      (node (ref "U16") (pin "12") (pinfunction "GND_12") (pintype "power_in"))
      (node (ref "U16") (pin "21") (pinfunction "A0_21") (pintype "input"))
      (node (ref "U16") (pin "3") (pinfunction "A2_3") (pintype "input"))
      (node (ref "U17") (pin "12") (pinfunction "GND_12") (pintype "power_in"))
      (node (ref "U17") (pin "2") (pinfunction "A1_2") (pintype "input"))
      (node (ref "U17") (pin "21") (pinfunction "A0_21") (pintype "input"))
      (node (ref "U17") (pin "3") (pinfunction "A2_3") (pintype "input"))
      (node (ref "U39") (pin "12") (pinfunction "GND_12") (pintype "power_in"))
      (node (ref "U39") (pin "2") (pinfunction "A1_2") (pintype "input"))
      (node (ref "U39") (pin "3") (pinfunction "A2_3") (pintype "input"))
      (node (ref "U4") (pin "2") (pinfunction "GND_2") (pintype "passive"))
      (node (ref "U5") (pin "3") (pinfunction "GND_3") (pintype "passive"))
      (node (ref "U5") (pin "4") (pinfunction "GND_4") (pintype "passive"))
      (node (ref "U6") (pin "2") (pinfunction "GND_2") (pintype "passive"))
      (node (ref "U7") (pin "3") (pinfunction "GND_3") (pintype "passive"))
      (node (ref "U7") (pin "4") (pinfunction "GND_4") (pintype "passive"))
      (node (ref "U8") (pin "2") (pinfunction "GND_2") (pintype "passive"))
      (node (ref "U9") (pin "3") (pinfunction "GND_3") (pintype "passive"))
      (node (ref "U9") (pin "4") (pinfunction "GND_4") (pintype "passive"))
    )
    (net (code "30") (name "GP14") (class "Default")
      (node (ref "U6") (pin "3") (pinfunction "A_3") (pintype "passive"))
    )
    (net (code "31") (name "GP15") (class "Default")
      (node (ref "R122") (pin "2") (pinfunction "2_2") (pintype "passive"))
      (node (ref "U17") (pin "1") (pinfunction "~{INT}_1") (pintype "open_collector"))
    )
    (net (code "32") (name "GP27") (class "Default")
      (node (ref "Q3") (pin "2") (pinfunction "S_2") (pintype "passive"))
      (node (ref "R39") (pin "2") (pinfunction "2_2") (pintype "passive"))
    )
    (net (code "33") (name "GP28") (class "Default")
      (node (ref "Q4") (pin "2") (pinfunction "S_2") (pintype "passive"))
      (node (ref "R40") (pin "2") (pinfunction "2_2") (pintype "passive"))
    )
    (net (code "34") (name "GP44") (class "Default")
      (node (ref "U14") (pin "3") (pinfunction "A_3") (pintype "passive"))
    )
    (net (code "35") (name "GP45") (class "Default")
      (node (ref "U12") (pin "3") (pinfunction "A_3") (pintype "passive"))
    )
    (net (code "36") (name "GP46") (class "Default")
      (node (ref "U10") (pin "3") (pinfunction "A_3") (pintype "passive"))
    )
    (net (code "37") (name "GP47") (class "Default")
      (node (ref "U8") (pin "3") (pinfunction "A_3") (pintype "passive"))
    )
    (net (code "38") (name "GP165") (class "Default")
      (node (ref "U4") (pin "3") (pinfunction "A_3") (pintype "passive"))
    )
    (net (code "39") (name "Net-(Q3-D)") (class "Default")
      (node (ref "Q3") (pin "3") (pinfunction "D_3") (pintype "passive"))
      (node (ref "R41") (pin "2") (pinfunction "2_2") (pintype "passive"))
      (node (ref "U4") (pin "4") (pinfunction "B_4") (pintype "passive"))
      (node (ref "U5") (pin "7") (pinfunction "Y1_7") (pintype "passive"))
    )
    (net (code "40") (name "Net-(Q4-D)") (class "Default")
      (node (ref "Q4") (pin "3") (pinfunction "D_3") (pintype "passive"))
      (node (ref "R42") (pin "2") (pinfunction "2_2") (pintype "passive"))
      (node (ref "U6") (pin "4") (pinfunction "B_4") (pintype "passive"))
      (node (ref "U7") (pin "7") (pinfunction "Y1_7") (pintype "passive"))
    )
    (net (code "41") (name "Net-(Q5-D)") (class "Default")
      (node (ref "Q5") (pin "3") (pinfunction "D_3") (pintype "passive"))
      (node (ref "R50") (pin "2") (pinfunction "2_2") (pintype "passive"))
      (node (ref "U17") (pin "23") (pinfunction "SDA_23") (pintype "bidirectional"))
      (node (ref "U39") (pin "23") (pinfunction "SDA_23") (pintype "bidirectional"))
    )
    (net (code "42") (name "Net-(Q6-D)") (class "Default")
      (node (ref "Q6") (pin "3") (pinfunction "D_3") (pintype "passive"))
      (node (ref "R51") (pin "2") (pinfunction "2_2") (pintype "passive"))
      (node (ref "U17") (pin "22") (pinfunction "SCL_22") (pintype "input"))
      (node (ref "U39") (pin "22") (pinfunction "SCL_22") (pintype "input"))
    )
    (net (code "43") (name "Net-(U*-R1,C1)") (class "Default")
      (node (ref "R12") (pin "1") (pinfunction "1_1") (pintype "passive"))
      (node (ref "R34") (pin "2") (pinfunction "2_2") (pintype "passive"))
      (node (ref "U*") (pin "6") (pinfunction "R1,C1_6") (pintype "passive"))
      (node (ref "U11") (pin "2") (pinfunction "INH_2") (pintype "passive"))
      (node (ref "U13") (pin "2") (pinfunction "INH_2") (pintype "passive"))
      (node (ref "U15") (pin "2") (pinfunction "INH_2") (pintype "passive"))
      (node (ref "U5") (pin "2") (pinfunction "INH_2") (pintype "passive"))
      (node (ref "U7") (pin "2") (pinfunction "INH_2") (pintype "passive"))
      (node (ref "U9") (pin "2") (pinfunction "INH_2") (pintype "passive"))
    )
    (net (code "44") (name "Net-(U8-B)") (class "Default")
      (node (ref "U8") (pin "4") (pinfunction "B_4") (pintype "passive"))
      (node (ref "U9") (pin "7") (pinfunction "Y1_7") (pintype "passive"))
    )
    (net (code "45") (name "Net-(U10-B)") (class "Default")
      (node (ref "U10") (pin "4") (pinfunction "B_4") (pintype "passive"))
      (node (ref "U11") (pin "7") (pinfunction "Y1_7") (pintype "passive"))
    )
    (net (code "46") (name "Net-(U10-DIR)") (class "Default")
      (node (ref "R15") (pin "1") (pinfunction "1_1") (pintype "passive"))
      (node (ref "U10") (pin "5") (pinfunction "DIR_5") (pintype "passive"))
      (node (ref "U16") (pin "6") (pinfunction "P02_6") (pintype "bidirectional"))
    )
    (net (code "47") (name "Net-(U11-A)") (class "Default")
      (node (ref "R118") (pin "2") (pinfunction "2_2") (pintype "passive"))
      (node (ref "U11") (pin "5") (pinfunction "A_5") (pintype "passive"))
      (node (ref "U17") (pin "6") (pinfunction "P02_6") (pintype "bidirectional"))
    )
    (net (code "48") (name "Net-(U12-B)") (class "Default")
      (node (ref "U12") (pin "4") (pinfunction "B_4") (pintype "passive"))
      (node (ref "U13") (pin "7") (pinfunction "Y1_7") (pintype "passive"))
    )
    (net (code "49") (name "Net-(U12-DIR)") (class "Default")
      (node (ref "R14") (pin "1") (pinfunction "1_1") (pintype "passive"))
      (node (ref "U12") (pin "5") (pinfunction "DIR_5") (pintype "passive"))
      (node (ref "U16") (pin "5") (pinfunction "P01_5") (pintype "bidirectional"))
    )
    (net (code "50") (name "Net-(U13-A)") (class "Default")
      (node (ref "R117") (pin "2") (pinfunction "2_2") (pintype "passive"))
      (node (ref "U13") (pin "5") (pinfunction "A_5") (pintype "passive"))
      (node (ref "U17") (pin "5") (pinfunction "P01_5") (pintype "bidirectional"))
    )
    (net (code "51") (name "Net-(U14-B)") (class "Default")
      (node (ref "U14") (pin "4") (pinfunction "B_4") (pintype "passive"))
      (node (ref "U15") (pin "7") (pinfunction "Y1_7") (pintype "passive"))
    )
    (net (code "52") (name "Net-(U14-DIR)") (class "Default")
      (node (ref "R13") (pin "1") (pinfunction "1_1") (pintype "passive"))
      (node (ref "U14") (pin "5") (pinfunction "DIR_5") (pintype "passive"))
      (node (ref "U16") (pin "4") (pinfunction "P00_4") (pintype "bidirectional"))
    )
    (net (code "53") (name "Net-(U15-A)") (class "Default")
      (node (ref "R116") (pin "2") (pinfunction "2_2") (pintype "passive"))
      (node (ref "U15") (pin "5") (pinfunction "A_5") (pintype "passive"))
      (node (ref "U17") (pin "4") (pinfunction "P00_4") (pintype "bidirectional"))
    )
    (net (code "54") (name "Net-(U16-P03)") (class "Default")
      (node (ref "R16") (pin "1") (pinfunction "1_1") (pintype "passive"))
      (node (ref "U16") (pin "7") (pinfunction "P03_7") (pintype "bidirectional"))
      (node (ref "U8") (pin "5") (pinfunction "DIR_5") (pintype "passive"))
    )
    (net (code "55") (name "Net-(U16-P04)") (class "Default")
      (node (ref "R17") (pin "1") (pinfunction "1_1") (pintype "passive"))
      (node (ref "U16") (pin "8") (pinfunction "P04_8") (pintype "bidirectional"))
      (node (ref "U6") (pin "5") (pinfunction "DIR_5") (pintype "passive"))
    )
    (net (code "56") (name "Net-(U16-P05)") (class "Default")
      (node (ref "R18") (pin "1") (pinfunction "1_1") (pintype "passive"))
      (node (ref "U16") (pin "9") (pinfunction "P05_9") (pintype "bidirectional"))
      (node (ref "U4") (pin "5") (pinfunction "DIR_5") (pintype "passive"))
    )
    (net (code "57") (name "Net-(U17-P03)") (class "Default")
      (node (ref "R119") (pin "2") (pinfunction "2_2") (pintype "passive"))
      (node (ref "U17") (pin "7") (pinfunction "P03_7") (pintype "bidirectional"))
      (node (ref "U9") (pin "5") (pinfunction "A_5") (pintype "passive"))
    )
    (net (code "58") (name "Net-(U17-P04)") (class "Default")
      (node (ref "R120") (pin "2") (pinfunction "2_2") (pintype "passive"))
      (node (ref "U17") (pin "8") (pinfunction "P04_8") (pintype "bidirectional"))
      (node (ref "U7") (pin "5") (pinfunction "A_5") (pintype "passive"))
    )
    (net (code "59") (name "Net-(U17-P05)") (class "Default")
      (node (ref "R121") (pin "2") (pinfunction "2_2") (pintype "passive"))
      (node (ref "U17") (pin "9") (pinfunction "P05_9") (pintype "bidirectional"))
      (node (ref "U5") (pin "5") (pinfunction "A_5") (pintype "passive"))
    )
    (net (code "60") (name "Net-(U17-P10)") (class "Default")
      (node (ref "R52") (pin "2") (pinfunction "2_2") (pintype "passive"))
      (node (ref "U17") (pin "13") (pinfunction "P10_13") (pintype "bidirectional"))
    )
    (net (code "61") (name "Net-(U17-P11)") (class "Default")
      (node (ref "R53") (pin "2") (pinfunction "2_2") (pintype "passive"))
      (node (ref "U17") (pin "14") (pinfunction "P11_14") (pintype "bidirectional"))
    )
    (net (code "62") (name "Net-(U17-P12)") (class "Default")
      (node (ref "R54") (pin "2") (pinfunction "2_2") (pintype "passive"))
      (node (ref "U17") (pin "15") (pinfunction "P12_15") (pintype "bidirectional"))
    )
    (net (code "63") (name "Net-(U17-P13)") (class "Default")
      (node (ref "R55") (pin "2") (pinfunction "2_2") (pintype "passive"))
      (node (ref "U17") (pin "16") (pinfunction "P13_16") (pintype "bidirectional"))
    )
    (net (code "64") (name "Net-(U17-P14)") (class "Default")
      (node (ref "R56") (pin "2") (pinfunction "2_2") (pintype "passive"))
      (node (ref "U17") (pin "17") (pinfunction "P14_17") (pintype "bidirectional"))
    )
    (net (code "65") (name "Net-(U17-P15)") (class "Default")
      (node (ref "R57") (pin "2") (pinfunction "2_2") (pintype "passive"))
      (node (ref "U17") (pin "18") (pinfunction "P15_18") (pintype "bidirectional"))
    )
    (net (code "66") (name "Net-(U39-P00)") (class "Default")
      (node (ref "R64") (pin "2") (pinfunction "2_2") (pintype "passive"))
      (node (ref "U39") (pin "4") (pinfunction "P00_4") (pintype "bidirectional"))
    )
    (net (code "67") (name "Net-(U39-P01)") (class "Default")
      (node (ref "R65") (pin "2") (pinfunction "2_2") (pintype "passive"))
      (node (ref "U39") (pin "5") (pinfunction "P01_5") (pintype "bidirectional"))
    )
    (net (code "68") (name "Net-(U39-P02)") (class "Default")
      (node (ref "R66") (pin "2") (pinfunction "2_2") (pintype "passive"))
      (node (ref "U39") (pin "6") (pinfunction "P02_6") (pintype "bidirectional"))
    )
    (net (code "69") (name "Net-(U39-P03)") (class "Default")
      (node (ref "R67") (pin "2") (pinfunction "2_2") (pintype "passive"))
      (node (ref "U39") (pin "7") (pinfunction "P03_7") (pintype "bidirectional"))
    )
    (net (code "70") (name "Net-(U39-P04)") (class "Default")
      (node (ref "R68") (pin "2") (pinfunction "2_2") (pintype "passive"))
      (node (ref "U39") (pin "8") (pinfunction "P04_8") (pintype "bidirectional"))
    )
    (net (code "71") (name "Net-(U39-P05)") (class "Default")
      (node (ref "R69") (pin "2") (pinfunction "2_2") (pintype "passive"))
      (node (ref "U39") (pin "9") (pinfunction "P05_9") (pintype "bidirectional"))
    )
    (net (code "72") (name "Net-(U39-P06)") (class "Default")
      (node (ref "R70") (pin "2") (pinfunction "2_2") (pintype "passive"))
      (node (ref "U39") (pin "10") (pinfunction "P06_10") (pintype "bidirectional"))
    )
    (net (code "73") (name "Net-(U39-P07)") (class "Default")
      (node (ref "R71") (pin "2") (pinfunction "2_2") (pintype "passive"))
      (node (ref "U39") (pin "11") (pinfunction "P07_11") (pintype "bidirectional"))
    )
    (net (code "74") (name "Net-(U39-P10)") (class "Default")
      (node (ref "R58") (pin "2") (pinfunction "2_2") (pintype "passive"))
      (node (ref "U39") (pin "13") (pinfunction "P10_13") (pintype "bidirectional"))
    )
    (net (code "75") (name "Net-(U39-P11)") (class "Default")
      (node (ref "R59") (pin "2") (pinfunction "2_2") (pintype "passive"))
      (node (ref "U39") (pin "14") (pinfunction "P11_14") (pintype "bidirectional"))
    )
    (net (code "76") (name "Net-(U39-P12)") (class "Default")
      (node (ref "R60") (pin "2") (pinfunction "2_2") (pintype "passive"))
      (node (ref "U39") (pin "15") (pinfunction "P12_15") (pintype "bidirectional"))
    )
    (net (code "77") (name "Net-(U39-P13)") (class "Default")
      (node (ref "R61") (pin "2") (pinfunction "2_2") (pintype "passive"))
      (node (ref "U39") (pin "16") (pinfunction "P13_16") (pintype "bidirectional"))
    )
    (net (code "78") (name "Net-(U39-P14)") (class "Default")
      (node (ref "R62") (pin "2") (pinfunction "2_2") (pintype "passive"))
      (node (ref "U39") (pin "17") (pinfunction "P14_17") (pintype "bidirectional"))
    )
    (net (code "79") (name "Net-(U39-P15)") (class "Default")
      (node (ref "R63") (pin "2") (pinfunction "2_2") (pintype "passive"))
      (node (ref "U39") (pin "18") (pinfunction "P15_18") (pintype "bidirectional"))
    )
    (net (code "80") (name "SHLD_RESET") (class "Default")
      (node (ref "U17") (pin "10") (pinfunction "P06_10") (pintype "bidirectional"))
      (node (ref "U17") (pin "20") (pinfunction "P17_20") (pintype "bidirectional"))
    )
    (net (code "81") (name "SPI_CLK_SEL") (class "Default")
      (node (ref "U16") (pin "16") (pinfunction "P13_16") (pintype "bidirectional"))
    )
    (net (code "82") (name "SPI_FS_SEL") (class "Default")
      (node (ref "U16") (pin "13") (pinfunction "P10_13") (pintype "bidirectional"))
    )
    (net (code "83") (name "SPI_RXD_SEL") (class "Default")
      (node (ref "U16") (pin "15") (pinfunction "P12_15") (pintype "bidirectional"))
    )
    (net (code "84") (name "SPI_TXD_SEL") (class "Default")
      (node (ref "U16") (pin "14") (pinfunction "P11_14") (pintype "bidirectional"))
    )
    (net (code "85") (name "TRI_STATE_ALL") (class "Default")
      (node (ref "R35") (pin "1") (pinfunction "1_1") (pintype "passive"))
      (node (ref "U*") (pin "5") (pinfunction "ON/OFF_5") (pintype "passive"))
      (node (ref "U17") (pin "19") (pinfunction "P16_19") (pintype "bidirectional"))
    )
    (net (code "86") (name "V_1P80") (class "Default")
      (node (ref "C15") (pin "2") (pinfunction "2_2") (pintype "passive"))
      (node (ref "C16") (pin "2") (pinfunction "2_2") (pintype "passive"))
      (node (ref "C17") (pin "2") (pinfunction "2_2") (pintype "passive"))
      (node (ref "C18") (pin "2") (pinfunction "2_2") (pintype "passive"))
      (node (ref "C19") (pin "2") (pinfunction "2_2") (pintype "passive"))
      (node (ref "C20") (pin "2") (pinfunction "2_2") (pintype "passive"))
      (node (ref "C22") (pin "2") (pinfunction "2_2") (pintype "passive"))
      (node (ref "Q3") (pin "1") (pinfunction "G_1") (pintype "passive"))
      (node (ref "Q4") (pin "1") (pinfunction "G_1") (pintype "passive"))
      (node (ref "Q5") (pin "1") (pinfunction "G_1") (pintype "passive"))
      (node (ref "Q6") (pin "1") (pinfunction "G_1") (pintype "passive"))
      (node (ref "R39") (pin "1") (pinfunction "1_1") (pintype "passive"))
      (node (ref "R40") (pin "1") (pinfunction "1_1") (pintype "passive"))
      (node (ref "R43") (pin "1") (pinfunction "1_1") (pintype "passive"))
      (node (ref "R44") (pin "1") (pinfunction "1_1") (pintype "passive"))
      (node (ref "U10") (pin "1") (pinfunction "VCCA_1") (pintype "passive"))
      (node (ref "U12") (pin "1") (pinfunction "VCCA_1") (pintype "passive"))
      (node (ref "U14") (pin "1") (pinfunction "VCCA_1") (pintype "passive"))
      (node (ref "U4") (pin "1") (pinfunction "VCCA_1") (pintype "passive"))
      (node (ref "U6") (pin "1") (pinfunction "VCCA_1") (pintype "passive"))
      (node (ref "U8") (pin "1") (pinfunction "VCCA_1") (pintype "passive"))
    )
    (net (code "87") (name "V_1P80_IO") (class "Default")
      (node (ref "C21") (pin "2") (pinfunction "2_2") (pintype "passive"))
      (node (ref "R122") (pin "1") (pinfunction "1_1") (pintype "passive"))
      (node (ref "U16") (pin "2") (pinfunction "A1_2") (pintype "input"))
      (node (ref "U16") (pin "24") (pinfunction "VCC_24") (pintype "power_in"))
    )
    (net (code "88") (name "V_SHIELD") (class "Default")
      (node (ref "C23") (pin "2") (pinfunction "2_2") (pintype "passive"))
      (node (ref "C24") (pin "2") (pinfunction "2_2") (pintype "passive"))
      (node (ref "C25") (pin "2") (pinfunction "2_2") (pintype "passive"))
      (node (ref "C28") (pin "2") (pinfunction "2_2") (pintype "passive"))
      (node (ref "C29") (pin "2") (pinfunction "2_2") (pintype "passive"))
      (node (ref "C30") (pin "2") (pinfunction "2_2") (pintype "passive"))
      (node (ref "R12") (pin "2") (pinfunction "2_2") (pintype "passive"))
      (node (ref "R34") (pin "1") (pinfunction "1_1") (pintype "passive"))
      (node (ref "R41") (pin "1") (pinfunction "1_1") (pintype "passive"))
      (node (ref "R42") (pin "1") (pinfunction "1_1") (pintype "passive"))
      (node (ref "U*") (pin "4") (pinfunction "Vin,R1_4") (pintype "passive"))
      (node (ref "U11") (pin "8") (pinfunction "VCC_8") (pintype "passive"))
      (node (ref "U13") (pin "8") (pinfunction "VCC_8") (pintype "passive"))
      (node (ref "U15") (pin "8") (pinfunction "VCC_8") (pintype "passive"))
      (node (ref "U5") (pin "8") (pinfunction "VCC_8") (pintype "passive"))
      (node (ref "U7") (pin "8") (pinfunction "VCC_8") (pintype "passive"))
      (node (ref "U9") (pin "8") (pinfunction "VCC_8") (pintype "passive"))
    )
    (net (code "89") (name "V_SHIELD_SW") (class "Default")
      (node (ref "R125") (pin "1") (pinfunction "1_1") (pintype "passive"))
      (node (ref "U*") (pin "2") (pinfunction "Vout,C1_2") (pintype "passive"))
      (node (ref "U*") (pin "3") (pinfunction "Vout,C1_3") (pintype "passive"))
      (node (ref "U10") (pin "6") (pinfunction "VCCB_6") (pintype "passive"))
      (node (ref "U12") (pin "6") (pinfunction "VCCB_6") (pintype "passive"))
      (node (ref "U14") (pin "6") (pinfunction "VCCB_6") (pintype "passive"))
      (node (ref "U4") (pin "6") (pinfunction "VCCB_6") (pintype "passive"))
      (node (ref "U6") (pin "6") (pinfunction "VCCB_6") (pintype "passive"))
      (node (ref "U8") (pin "6") (pinfunction "VCCB_6") (pintype "passive"))
    )
    (net (code "90") (name "V_SHLD_IO") (class "Default")
      (node (ref "C26") (pin "2") (pinfunction "2_2") (pintype "passive"))
      (node (ref "C27") (pin "2") (pinfunction "2_2") (pintype "passive"))
      (node (ref "R116") (pin "1") (pinfunction "1_1") (pintype "passive"))
      (node (ref "R117") (pin "1") (pinfunction "1_1") (pintype "passive"))
      (node (ref "R118") (pin "1") (pinfunction "1_1") (pintype "passive"))
      (node (ref "R119") (pin "1") (pinfunction "1_1") (pintype "passive"))
      (node (ref "R120") (pin "1") (pinfunction "1_1") (pintype "passive"))
      (node (ref "R121") (pin "1") (pinfunction "1_1") (pintype "passive"))
      (node (ref "R50") (pin "1") (pinfunction "1_1") (pintype "passive"))
      (node (ref "R51") (pin "1") (pinfunction "1_1") (pintype "passive"))
      (node (ref "U17") (pin "24") (pinfunction "VCC_24") (pintype "power_in"))
      (node (ref "U39") (pin "21") (pinfunction "A0_21") (pintype "input"))
      (node (ref "U39") (pin "24") (pinfunction "VCC_24") (pintype "power_in"))
    )
    (net (code "91") (name "unconnected-(R44-Pad2)") (class "Default")
      (node (ref "R44") (pin "2") (pinfunction "2_2") (pintype "passive"))
    )
    (net (code "92") (name "unconnected-(U16-P06-Pad10)") (class "Default")
      (node (ref "U16") (pin "10") (pinfunction "P06_10") (pintype "bidirectional"))
    )
    (net (code "93") (name "unconnected-(U16-P07-Pad11)") (class "Default")
      (node (ref "U16") (pin "11") (pinfunction "P07_11") (pintype "bidirectional"))
    )
    (net (code "94") (name "unconnected-(U16-P14-Pad17)") (class "Default")
      (node (ref "U16") (pin "17") (pinfunction "P14_17") (pintype "bidirectional"))
    )
    (net (code "95") (name "unconnected-(U16-P15-Pad18)") (class "Default")
      (node (ref "U16") (pin "18") (pinfunction "P15_18") (pintype "bidirectional"))
    )
    (net (code "96") (name "unconnected-(U16-P16-Pad19)") (class "Default")
      (node (ref "U16") (pin "19") (pinfunction "P16_19") (pintype "bidirectional"))
    )
    (net (code "97") (name "unconnected-(U16-P17-Pad20)") (class "Default")
      (node (ref "U16") (pin "20") (pinfunction "P17_20") (pintype "bidirectional"))
    )
    (net (code "98") (name "unconnected-(U16-~{INT}-Pad1)") (class "Default")
      (node (ref "U16") (pin "1") (pinfunction "~{INT}_1") (pintype "open_collector"))
    )
    (net (code "99") (name "unconnected-(U17-P07-Pad11)") (class "Default")
      (node (ref "U17") (pin "11") (pinfunction "P07_11") (pintype "bidirectional"))
    )
    (net (code "100") (name "unconnected-(U39-P16-Pad19)") (class "Default")
      (node (ref "U39") (pin "19") (pinfunction "P16_19") (pintype "bidirectional"))
    )
    (net (code "101") (name "unconnected-(U39-P17-Pad20)") (class "Default")
      (node (ref "U39") (pin "20") (pinfunction "P17_20") (pintype "bidirectional"))
    )
    (net (code "102") (name "unconnected-(U39-~{INT}-Pad1)") (class "Default")
      (node (ref "U39") (pin "1") (pinfunction "~{INT}_1") (pintype "open_collector"))
    )
  )
)
